# SCH_rickrollcard_2024-07-06.net
KiCad netlist of a schematic drawn in EasyEDA
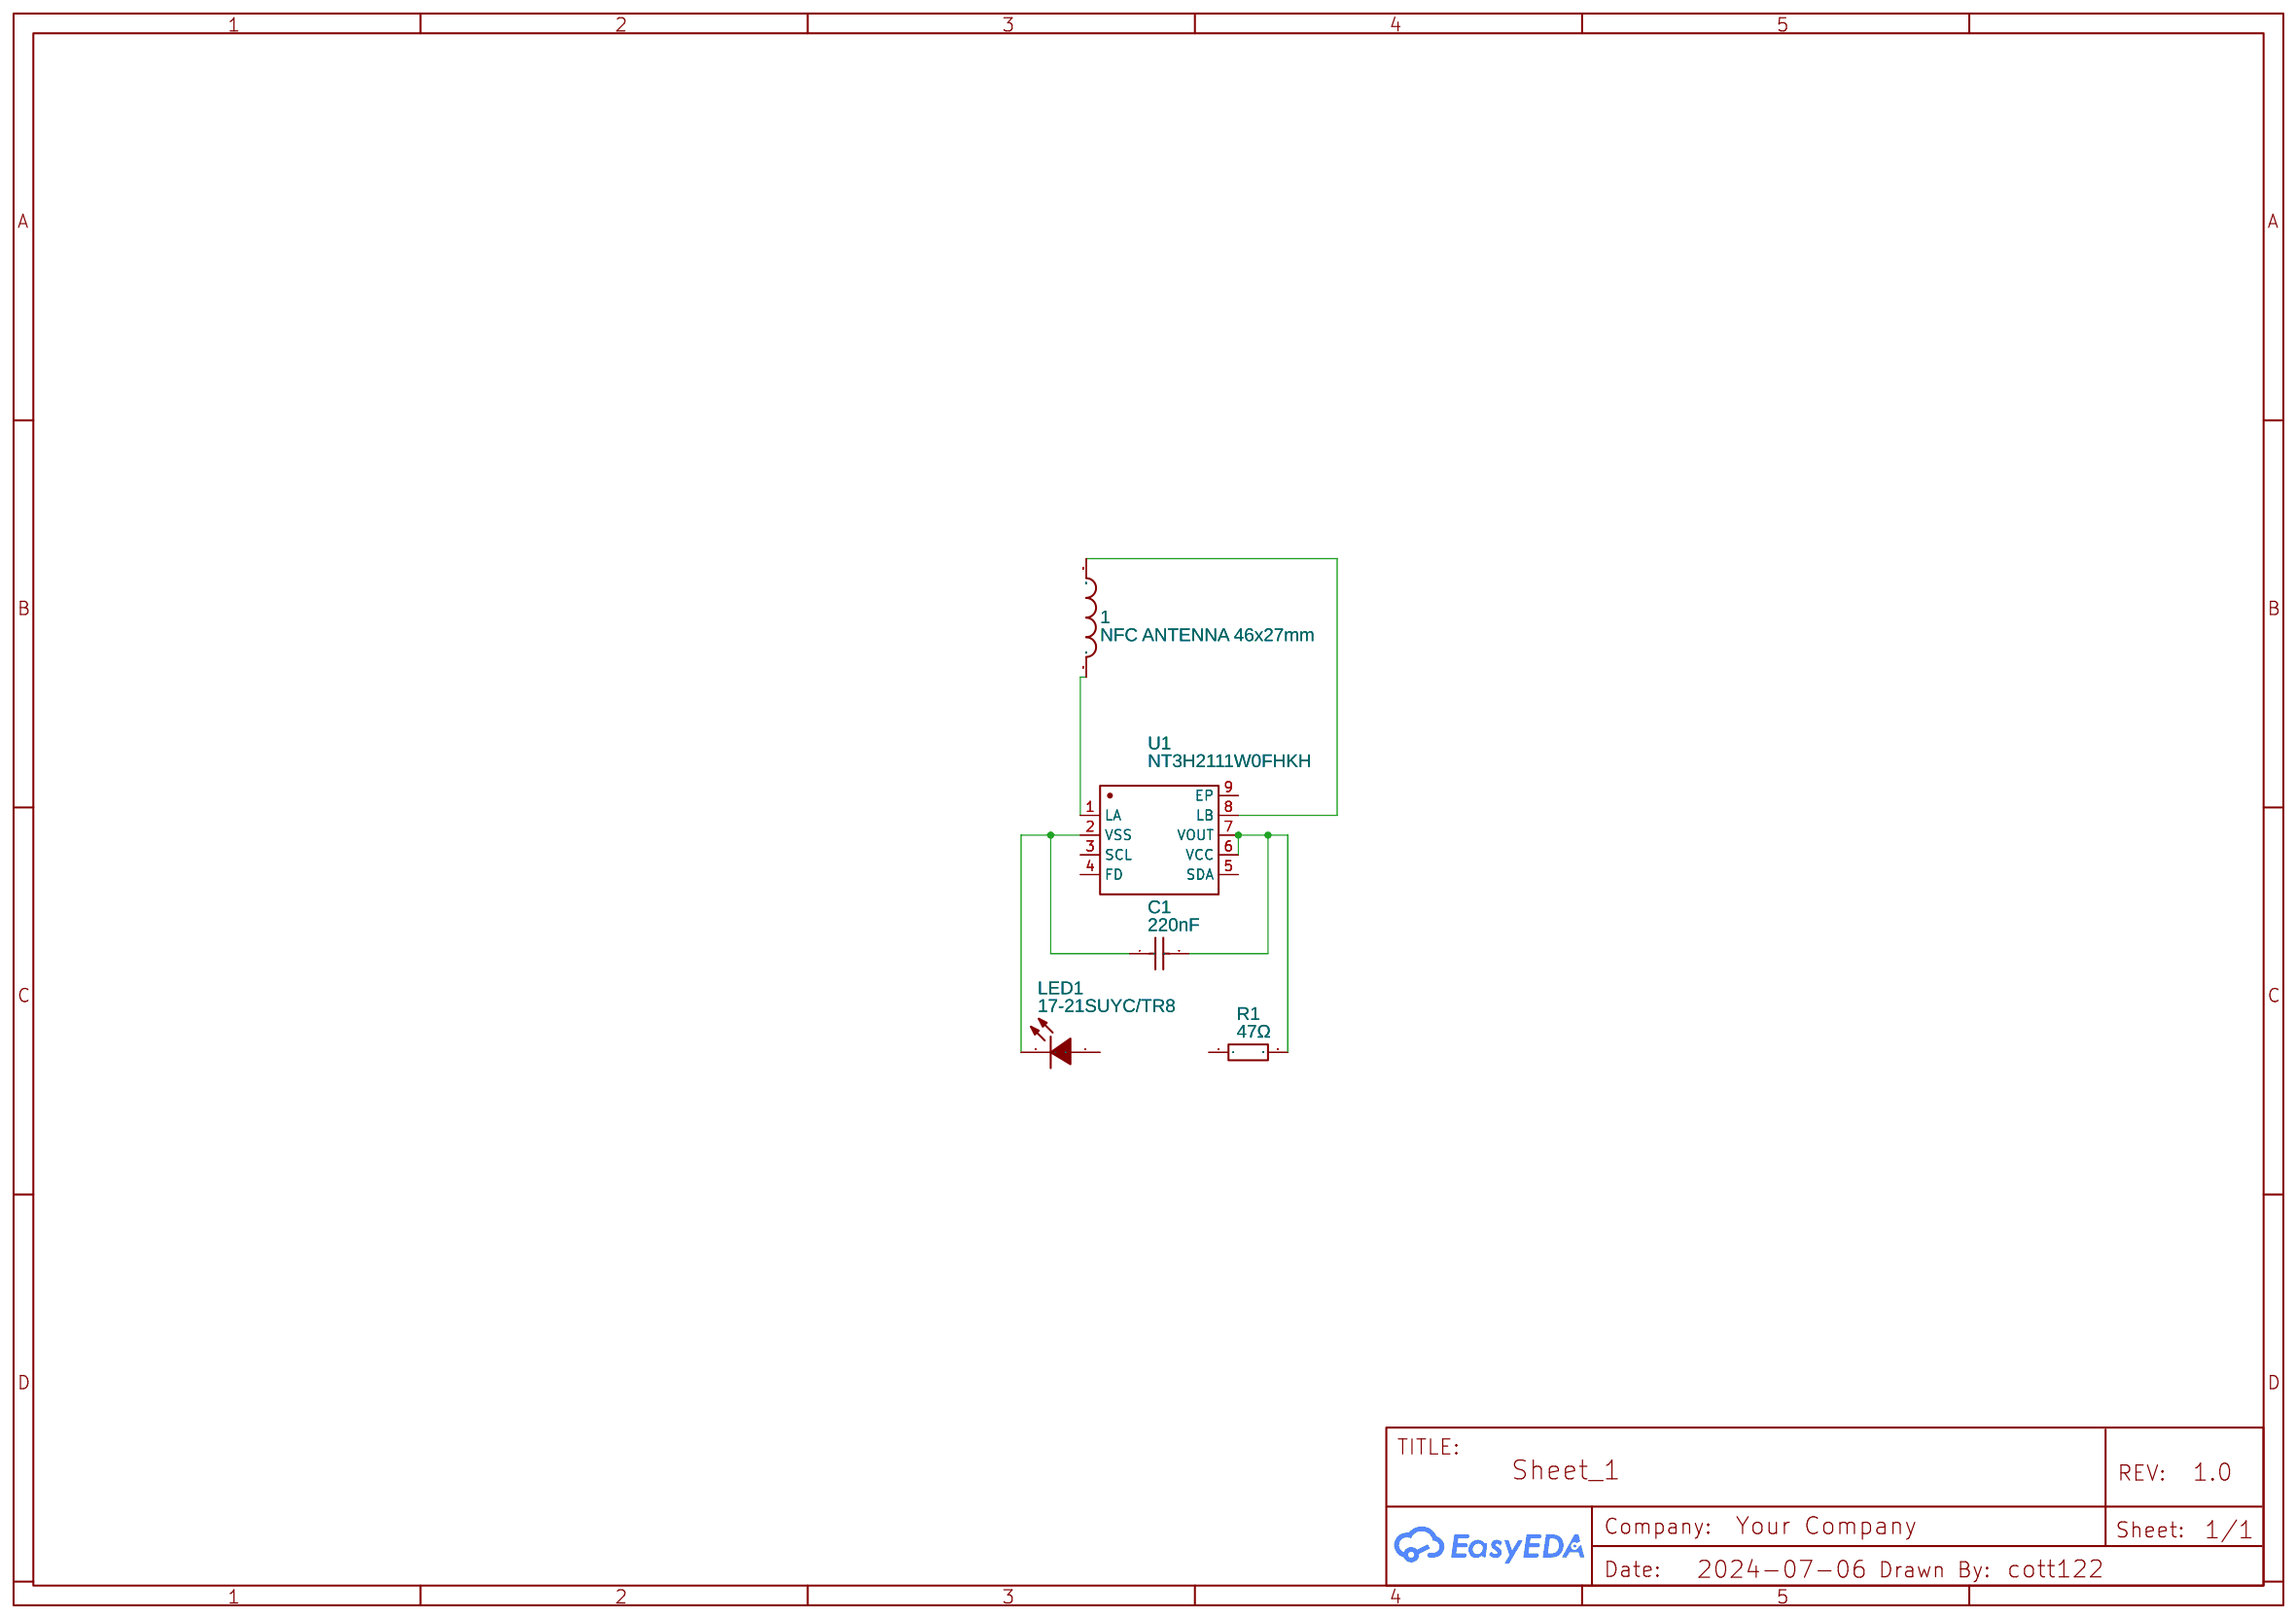
[diagram p0: schematic sheet]

(export (version "E")
  (design (tool "Eeschema 10.0.6"))
  (components
    (comp (ref "1") (value "NFC ANTENNA 46x27mm") (libsource (lib "") (part "NFC ANTENNA 46x27mm")))
    (comp (ref "C1")
      (value "220nF")
      (fields
        (field (name "Manufacturer Part") "CL10B224KA8NNNC")
        (field (name "Manufacturer") "SAMSUNG(三星)")
      )
      (libsource (lib "") (part "CL10B224KA8NNNC"))
    )
    (comp (ref "LED1")
      (value "17-21SUYC/TR8")
      (fields (field (name "Manufacturer Part") "KT-0805黄灯") (field (name "Manufacturer") "KENTO"))
      (libsource (lib "") (part "17-21SUYC/TR8"))
    )
    (comp (ref "R1")
      (value "47Ω")
      (fields
        (field (name "Manufacturer Part") "0603WAF470JT5E")
        (field (name "Manufacturer") "UNI-ROYAL(厚声)")
      )
      (libsource (lib "") (part "0603WAF470JT5E"))
    )
    (comp (ref "U1")
      (value "NT3H2111W0FHKH")
      (fields (field (name "Manufacturer") "NXP(恩智浦)"))
      (libsource (lib "") (part "NT3H2111W0FHKH"))
    )
  )
  (nets
    (net (code "1") (name "Net-(LED1--)") (class "Default")
      (node (ref "C1") (pin "1") (pinfunction "1_1") (pintype "input"))
      (node (ref "LED1") (pin "2") (pinfunction "-_2") (pintype "unspecified"))
      (node (ref "U1") (pin "2") (pinfunction "VSS_2") (pintype "unspecified"))
    )
    (net (code "2") (name "Net-(U1-LA)") (class "Default")
      (node (ref "1") (pin "P$2") (pinfunction "P$2_P$2") (pintype "bidirectional"))
      (node (ref "U1") (pin "1") (pinfunction "LA_1") (pintype "unspecified"))
    )
    (net (code "3") (name "Net-(U1-LB)") (class "Default")
      (node (ref "1") (pin "P$1") (pinfunction "P$1_P$1") (pintype "bidirectional"))
      (node (ref "U1") (pin "8") (pinfunction "LB_8") (pintype "unspecified"))
    )
    (net (code "4") (name "Net-(U1-VCC)") (class "Default")
      (node (ref "C1") (pin "2") (pinfunction "2_2") (pintype "input"))
      (node (ref "R1") (pin "2") (pinfunction "2_2") (pintype "input"))
      (node (ref "U1") (pin "6") (pinfunction "VCC_6") (pintype "unspecified"))
      (node (ref "U1") (pin "7") (pinfunction "VOUT_7") (pintype "unspecified"))
    )
    (net (code "5") (name "unconnected-(LED1-+-Pad1)") (class "Default")
      (node (ref "LED1") (pin "1") (pinfunction "+_1") (pintype "unspecified"))
    )
    (net (code "6") (name "unconnected-(R1-Pad1)") (class "Default")
      (node (ref "R1") (pin "1") (pinfunction "1_1") (pintype "input"))
    )
    (net (code "7") (name "unconnected-(U1-EP-Pad9)") (class "Default")
      (node (ref "U1") (pin "9") (pinfunction "EP_9") (pintype "unspecified"))
    )
    (net (code "8") (name "unconnected-(U1-FD-Pad4)") (class "Default")
      (node (ref "U1") (pin "4") (pinfunction "FD_4") (pintype "unspecified"))
    )
    (net (code "9") (name "unconnected-(U1-SCL-Pad3)") (class "Default")
      (node (ref "U1") (pin "3") (pinfunction "SCL_3") (pintype "unspecified"))
    )
    (net (code "10") (name "unconnected-(U1-SDA-Pad5)") (class "Default")
      (node (ref "U1") (pin "5") (pinfunction "SDA_5") (pintype "unspecified"))
    )
  )
)
